# thermal_monitor.net
KiCad netlist of a schematic drawn in Altium Designer
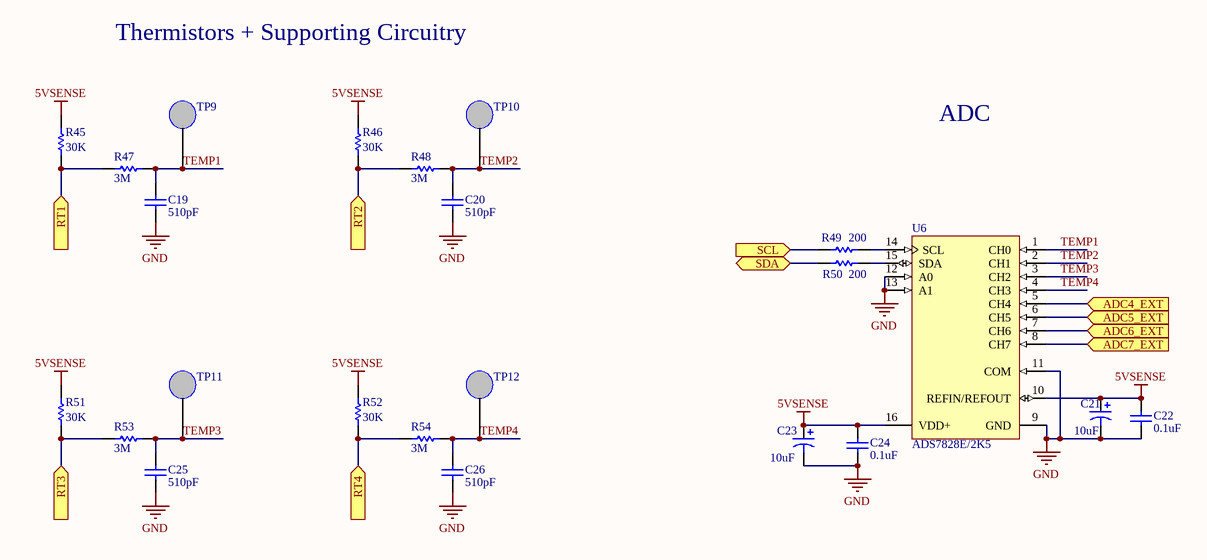
[diagram p0: thermal_monitor.SchDoc]

(export (version "E")
  (design (tool "Eeschema 10.0.6"))
  (components
    (comp (ref "C19")
      (value "510pF")
      (footprint "CAPC1608N")
      (description "Capacitor")
      (fields
        (field (name "MANUFACTURER") "Murata Electronics North America")
        (field (name "MANUFACTURER PART NUMBER") "GRM1885C2A511JA01D")
        (field (name "PUBLISHER") "Altium Limited")
      )
      (libsource (lib "Miscellaneous Devices") (part "Cap"))
    )
    (comp (ref "C20")
      (value "510pF")
      (footprint "CAPC1608N")
      (description "Capacitor")
      (fields
        (field (name "MANUFACTURER") "Murata Electronics North America")
        (field (name "MANUFACTURER PART NUMBER") "GRM1885C2A511JA01D")
        (field (name "PUBLISHER") "Altium Limited")
      )
      (libsource (lib "Miscellaneous Devices") (part "Cap"))
    )
    (comp (ref "C21")
      (value "10uF")
      (footprint "CAPC2012N")
      (description "Polarized Capacitor (Radial)")
      (fields
        (field (name "MANUFACTURER") "AVX Corporation")
        (field (name "MANUFACTURER PART NUMBER") "TACL106M010RTA")
        (field (name "PUBLISHER") "Altium Limited")
      )
      (libsource (lib "Miscellaneous Devices") (part "Cap Pol1"))
    )
    (comp (ref "C22")
      (value "0.1uF")
      (footprint "CAPC1608N")
      (description "Capacitor")
      (fields
        (field (name "MANUFACTURER") "Murata Electronics North America")
        (field (name "MANUFACTURER PART NUMBER") "GRM188R71H104JA93D")
        (field (name "PUBLISHER") "Altium Limited")
      )
      (libsource (lib "Miscellaneous Devices") (part "Cap"))
    )
    (comp (ref "C23")
      (value "10uF")
      (footprint "CAPC2012N")
      (description "Polarized Capacitor (Radial)")
      (fields
        (field (name "MANUFACTURER") "AVX Corporation")
        (field (name "MANUFACTURER PART NUMBER") "TACL106M010RTA")
        (field (name "PUBLISHER") "Altium Limited")
      )
      (libsource (lib "Miscellaneous Devices") (part "Cap Pol1"))
    )
    (comp (ref "C24")
      (value "0.1uF")
      (footprint "CAPC1608N")
      (description "Capacitor")
      (fields
        (field (name "MANUFACTURER") "Murata Electronics North America")
        (field (name "MANUFACTURER PART NUMBER") "GRM188R71H104JA93D")
        (field (name "PUBLISHER") "Altium Limited")
      )
      (libsource (lib "Miscellaneous Devices") (part "Cap"))
    )
    (comp (ref "C25")
      (value "510pF")
      (footprint "CAPC1608N")
      (description "Capacitor")
      (fields
        (field (name "MANUFACTURER") "Murata Electronics North America")
        (field (name "MANUFACTURER PART NUMBER") "GRM1885C2A511JA01D")
        (field (name "PUBLISHER") "Altium Limited")
      )
      (libsource (lib "Miscellaneous Devices") (part "Cap"))
    )
    (comp (ref "C26")
      (value "510pF")
      (footprint "CAPC1608N")
      (description "Capacitor")
      (fields
        (field (name "MANUFACTURER") "Murata Electronics North America")
        (field (name "MANUFACTURER PART NUMBER") "GRM1885C2A511JA01D")
        (field (name "PUBLISHER") "Altium Limited")
      )
      (libsource (lib "Miscellaneous Devices") (part "Cap"))
    )
    (comp (ref "R45")
      (value "30K")
      (footprint "RESC1608N")
      (description "Resistor")
      (fields
        (field (name "MANUFACTURER") "Yageo")
        (field (name "MANUFACTURER PART NUMBER") "RT0603DRD0730KL")
        (field (name "PUBLISHER") "Altium Limited")
      )
      (libsource (lib "Miscellaneous Devices") (part "Res1"))
    )
    (comp (ref "R46")
      (value "30K")
      (footprint "RESC1608N")
      (description "Resistor")
      (fields
        (field (name "MANUFACTURER") "Yageo")
        (field (name "MANUFACTURER PART NUMBER") "RT0603DRD0730KL")
        (field (name "PUBLISHER") "Altium Limited")
      )
      (libsource (lib "Miscellaneous Devices") (part "Res1"))
    )
    (comp (ref "R47")
      (value "3M")
      (footprint "RESC1608N")
      (description "Resistor")
      (fields
        (field (name "MANUFACTURER") "Yageo")
        (field (name "MANUFACTURER PART NUMBER") "RC0603JR-073ML")
        (field (name "PUBLISHER") "Altium Limited")
      )
      (libsource (lib "Miscellaneous Devices") (part "Res1"))
    )
    (comp (ref "R48")
      (value "3M")
      (footprint "RESC1608N")
      (description "Resistor")
      (fields
        (field (name "MANUFACTURER") "Yageo")
        (field (name "MANUFACTURER PART NUMBER") "RC0603JR-073ML")
        (field (name "PUBLISHER") "Altium Limited")
      )
      (libsource (lib "Miscellaneous Devices") (part "Res1"))
    )
    (comp (ref "R49")
      (value "200")
      (footprint "RESC1608N")
      (description "Resistor")
      (fields
        (field (name "MANUFACTURER") "Yageo")
        (field (name "MANUFACTURER PART NUMBER") "RC0603JR-07200RL")
        (field (name "PUBLISHER") "Altium Limited")
      )
      (libsource (lib "Miscellaneous Devices") (part "Res1"))
    )
    (comp (ref "R50")
      (value "200")
      (footprint "RESC1608N")
      (description "Resistor")
      (fields
        (field (name "MANUFACTURER") "Yageo")
        (field (name "MANUFACTURER PART NUMBER") "RC0603JR-07200RL")
        (field (name "PUBLISHER") "Altium Limited")
      )
      (libsource (lib "Miscellaneous Devices") (part "Res1"))
    )
    (comp (ref "R51")
      (value "30K")
      (footprint "RESC1608N")
      (description "Resistor")
      (fields
        (field (name "MANUFACTURER") "Yageo")
        (field (name "MANUFACTURER PART NUMBER") "RT0603DRD0730KL")
        (field (name "PUBLISHER") "Altium Limited")
      )
      (libsource (lib "Miscellaneous Devices") (part "Res1"))
    )
    (comp (ref "R52")
      (value "30K")
      (footprint "RESC1608N")
      (description "Resistor")
      (fields
        (field (name "MANUFACTURER") "Yageo")
        (field (name "MANUFACTURER PART NUMBER") "RT0603DRD0730KL")
        (field (name "PUBLISHER") "Altium Limited")
      )
      (libsource (lib "Miscellaneous Devices") (part "Res1"))
    )
    (comp (ref "R53")
      (value "3M")
      (footprint "RESC1608N")
      (description "Resistor")
      (fields
        (field (name "MANUFACTURER") "Yageo")
        (field (name "MANUFACTURER PART NUMBER") "RC0603JR-073ML")
        (field (name "PUBLISHER") "Altium Limited")
      )
      (libsource (lib "Miscellaneous Devices") (part "Res1"))
    )
    (comp (ref "R54")
      (value "3M")
      (footprint "RESC1608N")
      (description "Resistor")
      (fields
        (field (name "MANUFACTURER") "Yageo")
        (field (name "MANUFACTURER PART NUMBER") "RC0603JR-073ML")
        (field (name "PUBLISHER") "Altium Limited")
      )
      (libsource (lib "Miscellaneous Devices") (part "Res1"))
    )
    (comp (ref "TP9")
      (value "RT1")
      (footprint "TestPoint")
      (description "Test Point")
      (libsource (lib "common") (part "Ring_Terminal"))
    )
    (comp (ref "TP10")
      (value "RT2")
      (footprint "TestPoint")
      (description "Test Point")
      (libsource (lib "common") (part "Ring_Terminal"))
    )
    (comp (ref "TP11")
      (value "RT3")
      (footprint "TestPoint")
      (description "Test Point")
      (libsource (lib "common") (part "Ring_Terminal"))
    )
    (comp (ref "TP12")
      (value "RT4")
      (footprint "TestPoint")
      (description "Test Point")
      (libsource (lib "common") (part "Ring_Terminal"))
    )
    (comp (ref "U6")
      (value "ADS7828E/2K5")
      (footprint "TI-PW16_N")
      (description "IC ADC 12BIT 50KSPS 8CH 16-TSSOP")
      (fields (field (name "MANUFACTURER") "Texas Instruments"))
      (libsource (lib "TI Data Converters Analog to Digital Converter") (part "ADS7828E/2K5"))
    )
  )
  (nets
    (net (code "1") (name "/ADC4_EXT") (class "Default")
      (node (ref "U6") (pin "5") (pinfunction "CH4_5") (pintype "input"))
    )
    (net (code "2") (name "/ADC5_EXT") (class "Default")
      (node (ref "U6") (pin "6") (pinfunction "CH5_6") (pintype "input"))
    )
    (net (code "3") (name "/ADC6_EXT") (class "Default")
      (node (ref "U6") (pin "7") (pinfunction "CH6_7") (pintype "input"))
    )
    (net (code "4") (name "/ADC7_EXT") (class "Default")
      (node (ref "U6") (pin "8") (pinfunction "CH7_8") (pintype "input"))
    )
    (net (code "5") (name "/RT1") (class "Default")
      (node (ref "R45") (pin "1") (pinfunction "1_1") (pintype "passive"))
      (node (ref "R47") (pin "2") (pinfunction "2_2") (pintype "passive"))
    )
    (net (code "6") (name "/RT2") (class "Default")
      (node (ref "R46") (pin "1") (pinfunction "1_1") (pintype "passive"))
      (node (ref "R48") (pin "2") (pinfunction "2_2") (pintype "passive"))
    )
    (net (code "7") (name "/RT3") (class "Default")
      (node (ref "R51") (pin "1") (pinfunction "1_1") (pintype "passive"))
      (node (ref "R53") (pin "2") (pinfunction "2_2") (pintype "passive"))
    )
    (net (code "8") (name "/RT4") (class "Default")
      (node (ref "R52") (pin "1") (pinfunction "1_1") (pintype "passive"))
      (node (ref "R54") (pin "2") (pinfunction "2_2") (pintype "passive"))
    )
    (net (code "9") (name "/SCL") (class "Default")
      (node (ref "R49") (pin "1") (pinfunction "1_1") (pintype "passive"))
    )
    (net (code "10") (name "/SDA") (class "Default")
      (node (ref "R50") (pin "1") (pinfunction "1_1") (pintype "passive"))
    )
    (net (code "11") (name "/TEMP1") (class "Default")
      (node (ref "C19") (pin "2") (pinfunction "2_2") (pintype "passive"))
      (node (ref "R47") (pin "1") (pinfunction "1_1") (pintype "passive"))
      (node (ref "TP9") (pin "1") (pinfunction "1_1") (pintype "passive"))
      (node (ref "U6") (pin "1") (pinfunction "CH0_1") (pintype "input"))
    )
    (net (code "12") (name "/TEMP2") (class "Default")
      (node (ref "C20") (pin "2") (pinfunction "2_2") (pintype "passive"))
      (node (ref "R48") (pin "1") (pinfunction "1_1") (pintype "passive"))
      (node (ref "TP10") (pin "1") (pinfunction "1_1") (pintype "passive"))
      (node (ref "U6") (pin "2") (pinfunction "CH1_2") (pintype "input"))
    )
    (net (code "13") (name "/TEMP3") (class "Default")
      (node (ref "C25") (pin "2") (pinfunction "2_2") (pintype "passive"))
      (node (ref "R53") (pin "1") (pinfunction "1_1") (pintype "passive"))
      (node (ref "TP11") (pin "1") (pinfunction "1_1") (pintype "passive"))
      (node (ref "U6") (pin "3") (pinfunction "CH2_3") (pintype "input"))
    )
    (net (code "14") (name "/TEMP4") (class "Default")
      (node (ref "C26") (pin "2") (pinfunction "2_2") (pintype "passive"))
      (node (ref "R54") (pin "1") (pinfunction "1_1") (pintype "passive"))
      (node (ref "TP12") (pin "1") (pinfunction "1_1") (pintype "passive"))
      (node (ref "U6") (pin "4") (pinfunction "CH3_4") (pintype "input"))
    )
    (net (code "15") (name "5VSENSE") (class "Default")
      (node (ref "C21") (pin "1") (pinfunction "1_1") (pintype "passive"))
      (node (ref "C22") (pin "2") (pinfunction "2_2") (pintype "passive"))
      (node (ref "C23") (pin "1") (pinfunction "1_1") (pintype "passive"))
      (node (ref "C24") (pin "2") (pinfunction "2_2") (pintype "passive"))
      (node (ref "R45") (pin "2") (pinfunction "2_2") (pintype "passive"))
      (node (ref "R46") (pin "2") (pinfunction "2_2") (pintype "passive"))
      (node (ref "R51") (pin "2") (pinfunction "2_2") (pintype "passive"))
      (node (ref "R52") (pin "2") (pinfunction "2_2") (pintype "passive"))
      (node (ref "U6") (pin "10") (pinfunction "REFIN/REFOUT_10") (pintype "bidirectional"))
      (node (ref "U6") (pin "16") (pinfunction "VDD+_16") (pintype "power_in"))
    )
    (net (code "16") (name "GND") (class "Default")
      (node (ref "C19") (pin "1") (pinfunction "1_1") (pintype "passive"))
      (node (ref "C20") (pin "1") (pinfunction "1_1") (pintype "passive"))
      (node (ref "C21") (pin "2") (pinfunction "2_2") (pintype "passive"))
      (node (ref "C22") (pin "1") (pinfunction "1_1") (pintype "passive"))
      (node (ref "C23") (pin "2") (pinfunction "2_2") (pintype "passive"))
      (node (ref "C24") (pin "1") (pinfunction "1_1") (pintype "passive"))
      (node (ref "C25") (pin "1") (pinfunction "1_1") (pintype "passive"))
      (node (ref "C26") (pin "1") (pinfunction "1_1") (pintype "passive"))
      (node (ref "U6") (pin "11") (pinfunction "COM_11") (pintype "input"))
      (node (ref "U6") (pin "12") (pinfunction "A0_12") (pintype "input"))
      (node (ref "U6") (pin "13") (pinfunction "A1_13") (pintype "input"))
      (node (ref "U6") (pin "9") (pinfunction "GND_9") (pintype "power_in"))
    )
    (net (code "17") (name "Net-(U6-SCL)") (class "Default")
      (node (ref "R49") (pin "2") (pinfunction "2_2") (pintype "passive"))
      (node (ref "U6") (pin "14") (pinfunction "SCL_14") (pintype "input"))
    )
    (net (code "18") (name "Net-(U6-SDA)") (class "Default")
      (node (ref "R50") (pin "2") (pinfunction "2_2") (pintype "passive"))
      (node (ref "U6") (pin "15") (pinfunction "SDA_15") (pintype "bidirectional"))
    )
  )
)
